# Beambreak_Array_S_-_Receiver.net
KiCad netlist of a schematic drawn in Altium Designer
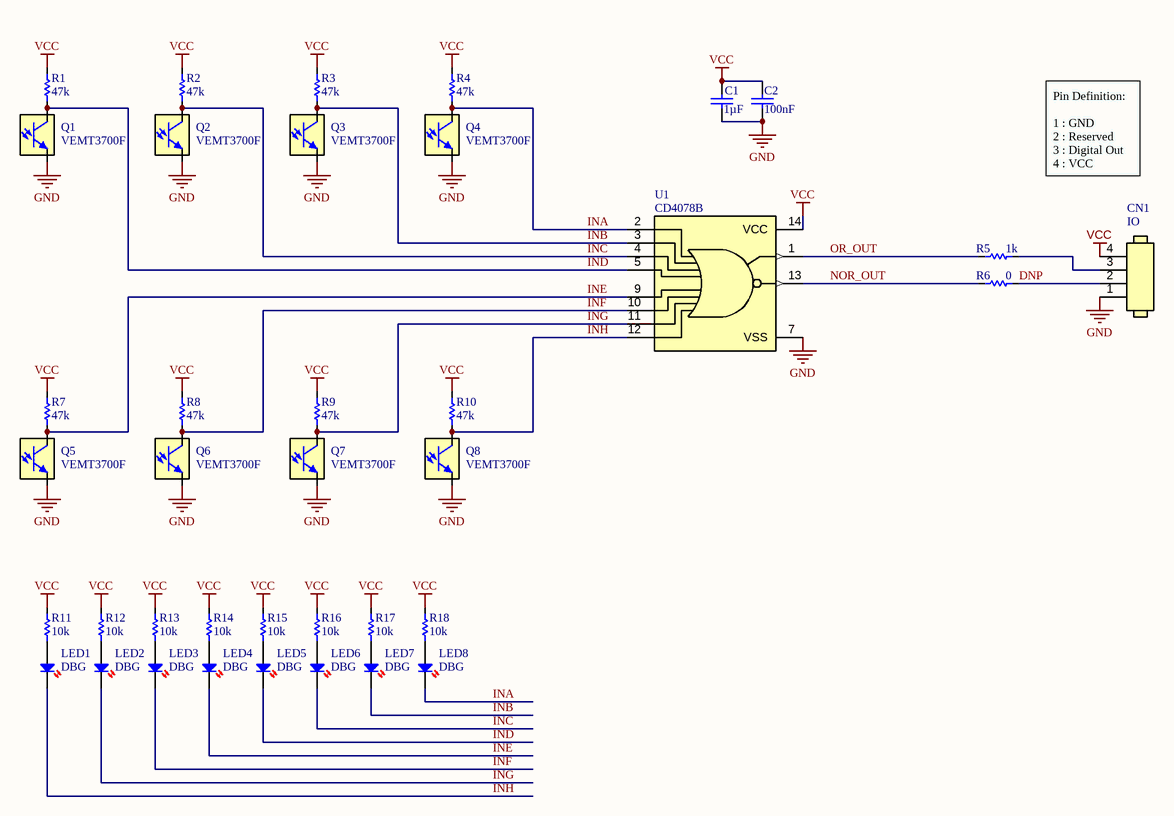
[diagram p0: Beambreak Array S - Receiver.SchDoc]

(export (version "E")
  (design (tool "Eeschema 10.0.6"))
  (components
    (comp (ref "C1")
      (value "1µF")
      (footprint "CAP_CHIP_0603")
      (description "0603 Multilayer Ceramic Capacitors MLCC")
      (fields (field (name "PARTNUMBER") "CL10A105KB8NNNC") (field (name "TOLERANCE") "10%"))
      (libsource (lib "Sainsbury Wellcome Centre") (part "Cap"))
    )
    (comp (ref "C2")
      (value "100nF")
      (footprint "CAP_CHIP_0603")
      (description "0603 Multilayer Ceramic Capacitors MLCC")
      (fields (field (name "TOLERANCE") "10%") (field (name "PARTNUMBER") "CC0603KRX7R9BB104"))
      (libsource (lib "Sainsbury Wellcome Centre") (part "Cap"))
    )
    (comp (ref "CN1")
      (value "IO")
      (footprint "MOLEX_1.25_4P")
      (description "Conn Shrouded Header (3 Sides) HDR 4 POS 1.25mm Solder ST Top Entry SMD PicoBlade™ T/R")
      (fields (field (name "PARTNUMBER") "53398-0471"))
      (libsource (lib "Sainsbury Wellcome Centre") (part "Wire to Board 1x4"))
    )
    (comp (ref "LED1")
      (value "DBG")
      (footprint "LED_CHIP_0805")
      (description "Red 0805 Light Emitting Diodes (LED) ROHS")
      (fields (field (name "PARTNUMBER") "NCD0805R1"))
      (libsource (lib "Sainsbury Wellcome Centre") (part "LED-RED"))
    )
    (comp (ref "LED2")
      (value "DBG")
      (footprint "LED_CHIP_0805")
      (description "Red 0805 Light Emitting Diodes (LED) ROHS")
      (fields (field (name "PARTNUMBER") "NCD0805R1"))
      (libsource (lib "Sainsbury Wellcome Centre") (part "LED-RED"))
    )
    (comp (ref "LED3")
      (value "DBG")
      (footprint "LED_CHIP_0805")
      (description "Red 0805 Light Emitting Diodes (LED) ROHS")
      (fields (field (name "PARTNUMBER") "NCD0805R1"))
      (libsource (lib "Sainsbury Wellcome Centre") (part "LED-RED"))
    )
    (comp (ref "LED4")
      (value "DBG")
      (footprint "LED_CHIP_0805")
      (description "Red 0805 Light Emitting Diodes (LED) ROHS")
      (fields (field (name "PARTNUMBER") "NCD0805R1"))
      (libsource (lib "Sainsbury Wellcome Centre") (part "LED-RED"))
    )
    (comp (ref "LED5")
      (value "DBG")
      (footprint "LED_CHIP_0805")
      (description "Red 0805 Light Emitting Diodes (LED) ROHS")
      (fields (field (name "PARTNUMBER") "NCD0805R1"))
      (libsource (lib "Sainsbury Wellcome Centre") (part "LED-RED"))
    )
    (comp (ref "LED6")
      (value "DBG")
      (footprint "LED_CHIP_0805")
      (description "Red 0805 Light Emitting Diodes (LED) ROHS")
      (fields (field (name "PARTNUMBER") "NCD0805R1"))
      (libsource (lib "Sainsbury Wellcome Centre") (part "LED-RED"))
    )
    (comp (ref "LED7")
      (value "DBG")
      (footprint "LED_CHIP_0805")
      (description "Red 0805 Light Emitting Diodes (LED) ROHS")
      (fields (field (name "PARTNUMBER") "NCD0805R1"))
      (libsource (lib "Sainsbury Wellcome Centre") (part "LED-RED"))
    )
    (comp (ref "LED8")
      (value "DBG")
      (footprint "LED_CHIP_0805")
      (description "Red 0805 Light Emitting Diodes (LED) ROHS")
      (fields (field (name "PARTNUMBER") "NCD0805R1"))
      (libsource (lib "Sainsbury Wellcome Centre") (part "LED-RED"))
    )
    (comp (ref "Q1")
      (value "VEMT3700F")
      (footprint "PT_3528_NPN")
      (description "No Phototransistor IR Chip Silicon 940nm 2-Pin PLCC T/R")
      (fields (field (name "PARTNUMBER") "VEMT3700F-GS08"))
      (libsource (lib "Sainsbury Wellcome Centre") (part "Phototransistors_1C2E"))
    )
    (comp (ref "Q2")
      (value "VEMT3700F")
      (footprint "PT_3528_NPN")
      (description "No Phototransistor IR Chip Silicon 940nm 2-Pin PLCC T/R")
      (fields (field (name "PARTNUMBER") "VEMT3700F-GS08"))
      (libsource (lib "Sainsbury Wellcome Centre") (part "Phototransistors_1C2E"))
    )
    (comp (ref "Q3")
      (value "VEMT3700F")
      (footprint "PT_3528_NPN")
      (description "No Phototransistor IR Chip Silicon 940nm 2-Pin PLCC T/R")
      (fields (field (name "PARTNUMBER") "VEMT3700F-GS08"))
      (libsource (lib "Sainsbury Wellcome Centre") (part "Phototransistors_1C2E"))
    )
    (comp (ref "Q4")
      (value "VEMT3700F")
      (footprint "PT_3528_NPN")
      (description "No Phototransistor IR Chip Silicon 940nm 2-Pin PLCC T/R")
      (fields (field (name "PARTNUMBER") "VEMT3700F-GS08"))
      (libsource (lib "Sainsbury Wellcome Centre") (part "Phototransistors_1C2E"))
    )
    (comp (ref "Q5")
      (value "VEMT3700F")
      (footprint "PT_3528_NPN")
      (description "No Phototransistor IR Chip Silicon 940nm 2-Pin PLCC T/R")
      (fields (field (name "PARTNUMBER") "VEMT3700F-GS08"))
      (libsource (lib "Sainsbury Wellcome Centre") (part "Phototransistors_1C2E"))
    )
    (comp (ref "Q6")
      (value "VEMT3700F")
      (footprint "PT_3528_NPN")
      (description "No Phototransistor IR Chip Silicon 940nm 2-Pin PLCC T/R")
      (fields (field (name "PARTNUMBER") "VEMT3700F-GS08"))
      (libsource (lib "Sainsbury Wellcome Centre") (part "Phototransistors_1C2E"))
    )
    (comp (ref "Q7")
      (value "VEMT3700F")
      (footprint "PT_3528_NPN")
      (description "No Phototransistor IR Chip Silicon 940nm 2-Pin PLCC T/R")
      (fields (field (name "PARTNUMBER") "VEMT3700F-GS08"))
      (libsource (lib "Sainsbury Wellcome Centre") (part "Phototransistors_1C2E"))
    )
    (comp (ref "Q8")
      (value "VEMT3700F")
      (footprint "PT_3528_NPN")
      (description "No Phototransistor IR Chip Silicon 940nm 2-Pin PLCC T/R")
      (fields (field (name "PARTNUMBER") "VEMT3700F-GS08"))
      (libsource (lib "Sainsbury Wellcome Centre") (part "Phototransistors_1C2E"))
    )
    (comp (ref "R1")
      (value "47k")
      (footprint "RES_CHIP_0603")
      (description "100mW Thick Film Resistors 75V ±100ppm/℃ ±1% 0603 Chip Resistor")
      (fields (field (name "TOLERANCE") "1%") (field (name "PARTNUMBER") "0603WAF4702T5E"))
      (libsource (lib "Sainsbury Wellcome Centre") (part "Res"))
    )
    (comp (ref "R2")
      (value "47k")
      (footprint "RES_CHIP_0603")
      (description "100mW Thick Film Resistors 75V ±100ppm/℃ ±1% 0603 Chip Resistor")
      (fields (field (name "TOLERANCE") "1%") (field (name "PARTNUMBER") "0603WAF4702T5E"))
      (libsource (lib "Sainsbury Wellcome Centre") (part "Res"))
    )
    (comp (ref "R3")
      (value "47k")
      (footprint "RES_CHIP_0603")
      (description "100mW Thick Film Resistors 75V ±100ppm/℃ ±1% 0603 Chip Resistor")
      (fields (field (name "TOLERANCE") "1%") (field (name "PARTNUMBER") "0603WAF4702T5E"))
      (libsource (lib "Sainsbury Wellcome Centre") (part "Res"))
    )
    (comp (ref "R4")
      (value "47k")
      (footprint "RES_CHIP_0603")
      (description "100mW Thick Film Resistors 75V ±100ppm/℃ ±1% 0603 Chip Resistor")
      (fields (field (name "TOLERANCE") "1%") (field (name "PARTNUMBER") "0603WAF4702T5E"))
      (libsource (lib "Sainsbury Wellcome Centre") (part "Res"))
    )
    (comp (ref "R5")
      (value "1k")
      (footprint "RES_CHIP_0603")
      (description "100mW Thick Film Resistors 75V ±100ppm/℃ ±1% 0603 Chip Resistor")
      (fields (field (name "PARTNUMBER") "0603WAF1001T5E") (field (name "TOLERANCE") "1%"))
      (libsource (lib "Sainsbury Wellcome Centre") (part "Res"))
    )
    (comp (ref "R6")
      (value "0")
      (footprint "RES_CHIP_0603")
      (description "100mW Thick Film Resistors 75V ±100ppm/℃ ±1% 0603 Chip Resistor")
      (fields
        (field (name "TOLERANCE") "1%")
        (field (name "PARTNUMBER") "0603WAF0000T5E")
        (field (name "LCSC PART N.") "DNP")
      )
      (libsource (lib "Sainsbury Wellcome Centre") (part "Res"))
    )
    (comp (ref "R7")
      (value "47k")
      (footprint "RES_CHIP_0603")
      (description "100mW Thick Film Resistors 75V ±100ppm/℃ ±1% 0603 Chip Resistor")
      (fields (field (name "TOLERANCE") "1%") (field (name "PARTNUMBER") "0603WAF4702T5E"))
      (libsource (lib "Sainsbury Wellcome Centre") (part "Res"))
    )
    (comp (ref "R8")
      (value "47k")
      (footprint "RES_CHIP_0603")
      (description "100mW Thick Film Resistors 75V ±100ppm/℃ ±1% 0603 Chip Resistor")
      (fields (field (name "TOLERANCE") "1%") (field (name "PARTNUMBER") "0603WAF4702T5E"))
      (libsource (lib "Sainsbury Wellcome Centre") (part "Res"))
    )
    (comp (ref "R9")
      (value "47k")
      (footprint "RES_CHIP_0603")
      (description "100mW Thick Film Resistors 75V ±100ppm/℃ ±1% 0603 Chip Resistor")
      (fields (field (name "TOLERANCE") "1%") (field (name "PARTNUMBER") "0603WAF4702T5E"))
      (libsource (lib "Sainsbury Wellcome Centre") (part "Res"))
    )
    (comp (ref "R10")
      (value "47k")
      (footprint "RES_CHIP_0603")
      (description "100mW Thick Film Resistors 75V ±100ppm/℃ ±1% 0603 Chip Resistor")
      (fields (field (name "TOLERANCE") "1%") (field (name "PARTNUMBER") "0603WAF4702T5E"))
      (libsource (lib "Sainsbury Wellcome Centre") (part "Res"))
    )
    (comp (ref "R11")
      (value "10k")
      (footprint "RES_CHIP_0603")
      (description "100mW Thick Film Resistors 75V ±100ppm/℃ ±1% 0603 Chip Resistor")
      (fields (field (name "PARTNUMBER") "0603WAF1002T5E") (field (name "TOLERANCE") "1%"))
      (libsource (lib "Sainsbury Wellcome Centre") (part "Res"))
    )
    (comp (ref "R12")
      (value "10k")
      (footprint "RES_CHIP_0603")
      (description "100mW Thick Film Resistors 75V ±100ppm/℃ ±1% 0603 Chip Resistor")
      (fields (field (name "PARTNUMBER") "0603WAF1002T5E") (field (name "TOLERANCE") "1%"))
      (libsource (lib "Sainsbury Wellcome Centre") (part "Res"))
    )
    (comp (ref "R13")
      (value "10k")
      (footprint "RES_CHIP_0603")
      (description "100mW Thick Film Resistors 75V ±100ppm/℃ ±1% 0603 Chip Resistor")
      (fields (field (name "PARTNUMBER") "0603WAF1002T5E") (field (name "TOLERANCE") "1%"))
      (libsource (lib "Sainsbury Wellcome Centre") (part "Res"))
    )
    (comp (ref "R14")
      (value "10k")
      (footprint "RES_CHIP_0603")
      (description "100mW Thick Film Resistors 75V ±100ppm/℃ ±1% 0603 Chip Resistor")
      (fields (field (name "PARTNUMBER") "0603WAF1002T5E") (field (name "TOLERANCE") "1%"))
      (libsource (lib "Sainsbury Wellcome Centre") (part "Res"))
    )
    (comp (ref "R15")
      (value "10k")
      (footprint "RES_CHIP_0603")
      (description "100mW Thick Film Resistors 75V ±100ppm/℃ ±1% 0603 Chip Resistor")
      (fields (field (name "PARTNUMBER") "0603WAF1002T5E") (field (name "TOLERANCE") "1%"))
      (libsource (lib "Sainsbury Wellcome Centre") (part "Res"))
    )
    (comp (ref "R16")
      (value "10k")
      (footprint "RES_CHIP_0603")
      (description "100mW Thick Film Resistors 75V ±100ppm/℃ ±1% 0603 Chip Resistor")
      (fields (field (name "PARTNUMBER") "0603WAF1002T5E") (field (name "TOLERANCE") "1%"))
      (libsource (lib "Sainsbury Wellcome Centre") (part "Res"))
    )
    (comp (ref "R17")
      (value "10k")
      (footprint "RES_CHIP_0603")
      (description "100mW Thick Film Resistors 75V ±100ppm/℃ ±1% 0603 Chip Resistor")
      (fields (field (name "PARTNUMBER") "0603WAF1002T5E") (field (name "TOLERANCE") "1%"))
      (libsource (lib "Sainsbury Wellcome Centre") (part "Res"))
    )
    (comp (ref "R18")
      (value "10k")
      (footprint "RES_CHIP_0603")
      (description "100mW Thick Film Resistors 75V ±100ppm/℃ ±1% 0603 Chip Resistor")
      (fields (field (name "PARTNUMBER") "0603WAF1002T5E") (field (name "TOLERANCE") "1%"))
      (libsource (lib "Sainsbury Wellcome Centre") (part "Res"))
    )
    (comp (ref "U1")
      (value "CD4078B")
      (footprint "SOIC14")
      (description "IC GATE NOR/OR 8INPUT 14SOIC NOR/OR Gate Configurable 1 Circuit 8 Input 14-SOIC")
      (fields (field (name "PARTNUMBER") "CD4078BM96"))
      (libsource (lib "Sainsbury Wellcome Centre") (part "CD4078B"))
    )
  )
  (nets
    (net (code "1") (name "/INA") (class "Default")
      (node (ref "LED8") (pin "1") (pinfunction "K_1") (pintype "passive"))
      (node (ref "Q4") (pin "1") (pinfunction "C_1") (pintype "passive"))
      (node (ref "R4") (pin "1") (pinfunction "1_1") (pintype "passive"))
      (node (ref "U1") (pin "2") (pinfunction "1A_2") (pintype "passive"))
    )
    (net (code "2") (name "/INB") (class "Default")
      (node (ref "LED7") (pin "1") (pinfunction "K_1") (pintype "passive"))
      (node (ref "Q3") (pin "1") (pinfunction "C_1") (pintype "passive"))
      (node (ref "R3") (pin "1") (pinfunction "1_1") (pintype "passive"))
      (node (ref "U1") (pin "3") (pinfunction "1A_3") (pintype "passive"))
    )
    (net (code "3") (name "/INC") (class "Default")
      (node (ref "LED6") (pin "1") (pinfunction "K_1") (pintype "passive"))
      (node (ref "Q2") (pin "1") (pinfunction "C_1") (pintype "passive"))
      (node (ref "R2") (pin "1") (pinfunction "1_1") (pintype "passive"))
      (node (ref "U1") (pin "4") (pinfunction "1A_4") (pintype "passive"))
    )
    (net (code "4") (name "/IND") (class "Default")
      (node (ref "LED5") (pin "1") (pinfunction "K_1") (pintype "passive"))
      (node (ref "Q1") (pin "1") (pinfunction "C_1") (pintype "passive"))
      (node (ref "R1") (pin "1") (pinfunction "1_1") (pintype "passive"))
      (node (ref "U1") (pin "5") (pinfunction "1A_5") (pintype "passive"))
    )
    (net (code "5") (name "/INE") (class "Default")
      (node (ref "LED4") (pin "1") (pinfunction "K_1") (pintype "passive"))
      (node (ref "Q5") (pin "1") (pinfunction "C_1") (pintype "passive"))
      (node (ref "R7") (pin "1") (pinfunction "1_1") (pintype "passive"))
      (node (ref "U1") (pin "9") (pinfunction "1B_9") (pintype "passive"))
    )
    (net (code "6") (name "/INF") (class "Default")
      (node (ref "LED3") (pin "1") (pinfunction "K_1") (pintype "passive"))
      (node (ref "Q6") (pin "1") (pinfunction "C_1") (pintype "passive"))
      (node (ref "R8") (pin "1") (pinfunction "1_1") (pintype "passive"))
      (node (ref "U1") (pin "10") (pinfunction "2A_10") (pintype "passive"))
    )
    (net (code "7") (name "/ING") (class "Default")
      (node (ref "LED2") (pin "1") (pinfunction "K_1") (pintype "passive"))
      (node (ref "Q7") (pin "1") (pinfunction "C_1") (pintype "passive"))
      (node (ref "R9") (pin "1") (pinfunction "1_1") (pintype "passive"))
      (node (ref "U1") (pin "11") (pinfunction "2B_11") (pintype "passive"))
    )
    (net (code "8") (name "/INH") (class "Default")
      (node (ref "LED1") (pin "1") (pinfunction "K_1") (pintype "passive"))
      (node (ref "Q8") (pin "1") (pinfunction "C_1") (pintype "passive"))
      (node (ref "R10") (pin "1") (pinfunction "1_1") (pintype "passive"))
      (node (ref "U1") (pin "12") (pinfunction "1A_12") (pintype "passive"))
    )
    (net (code "9") (name "/NOR_OUT") (class "Default")
      (node (ref "R6") (pin "1") (pinfunction "1_1") (pintype "passive"))
      (node (ref "U1") (pin "13") (pinfunction "OUT_13") (pintype "output"))
    )
    (net (code "10") (name "/OR_OUT") (class "Default")
      (node (ref "R5") (pin "2") (pinfunction "2_2") (pintype "passive"))
      (node (ref "U1") (pin "1") (pinfunction "~{OUT}_1") (pintype "output"))
    )
    (net (code "11") (name "GND") (class "Default")
      (node (ref "C1") (pin "2") (pinfunction "2_2") (pintype "passive"))
      (node (ref "C2") (pin "1") (pinfunction "1_1") (pintype "passive"))
      (node (ref "CN1") (pin "1") (pinfunction "1_1") (pintype "passive"))
      (node (ref "Q1") (pin "2") (pinfunction "E_2") (pintype "passive"))
      (node (ref "Q2") (pin "2") (pinfunction "E_2") (pintype "passive"))
      (node (ref "Q3") (pin "2") (pinfunction "E_2") (pintype "passive"))
      (node (ref "Q4") (pin "2") (pinfunction "E_2") (pintype "passive"))
      (node (ref "Q5") (pin "2") (pinfunction "E_2") (pintype "passive"))
      (node (ref "Q6") (pin "2") (pinfunction "E_2") (pintype "passive"))
      (node (ref "Q7") (pin "2") (pinfunction "E_2") (pintype "passive"))
      (node (ref "Q8") (pin "2") (pinfunction "E_2") (pintype "passive"))
      (node (ref "U1") (pin "7") (pinfunction "VSS_7") (pintype "power_in"))
    )
    (net (code "12") (name "Net-(CN1-Pad2)") (class "Default")
      (node (ref "CN1") (pin "2") (pinfunction "2_2") (pintype "passive"))
      (node (ref "R6") (pin "2") (pinfunction "2_2") (pintype "passive"))
    )
    (net (code "13") (name "Net-(CN1-Pad3)") (class "Default")
      (node (ref "CN1") (pin "3") (pinfunction "3_3") (pintype "passive"))
      (node (ref "R5") (pin "1") (pinfunction "1_1") (pintype "passive"))
    )
    (net (code "14") (name "Net-(LED1-A)") (class "Default")
      (node (ref "LED1") (pin "2") (pinfunction "A_2") (pintype "passive"))
      (node (ref "R11") (pin "1") (pinfunction "1_1") (pintype "passive"))
    )
    (net (code "15") (name "Net-(LED2-A)") (class "Default")
      (node (ref "LED2") (pin "2") (pinfunction "A_2") (pintype "passive"))
      (node (ref "R12") (pin "1") (pinfunction "1_1") (pintype "passive"))
    )
    (net (code "16") (name "Net-(LED3-A)") (class "Default")
      (node (ref "LED3") (pin "2") (pinfunction "A_2") (pintype "passive"))
      (node (ref "R13") (pin "1") (pinfunction "1_1") (pintype "passive"))
    )
    (net (code "17") (name "Net-(LED4-A)") (class "Default")
      (node (ref "LED4") (pin "2") (pinfunction "A_2") (pintype "passive"))
      (node (ref "R14") (pin "1") (pinfunction "1_1") (pintype "passive"))
    )
    (net (code "18") (name "Net-(LED5-A)") (class "Default")
      (node (ref "LED5") (pin "2") (pinfunction "A_2") (pintype "passive"))
      (node (ref "R15") (pin "1") (pinfunction "1_1") (pintype "passive"))
    )
    (net (code "19") (name "Net-(LED6-A)") (class "Default")
      (node (ref "LED6") (pin "2") (pinfunction "A_2") (pintype "passive"))
      (node (ref "R16") (pin "1") (pinfunction "1_1") (pintype "passive"))
    )
    (net (code "20") (name "Net-(LED7-A)") (class "Default")
      (node (ref "LED7") (pin "2") (pinfunction "A_2") (pintype "passive"))
      (node (ref "R17") (pin "1") (pinfunction "1_1") (pintype "passive"))
    )
    (net (code "21") (name "Net-(LED8-A)") (class "Default")
      (node (ref "LED8") (pin "2") (pinfunction "A_2") (pintype "passive"))
      (node (ref "R18") (pin "1") (pinfunction "1_1") (pintype "passive"))
    )
    (net (code "22") (name "VCC") (class "Default")
      (node (ref "C1") (pin "1") (pinfunction "1_1") (pintype "passive"))
      (node (ref "C2") (pin "2") (pinfunction "2_2") (pintype "passive"))
      (node (ref "CN1") (pin "4") (pinfunction "4_4") (pintype "passive"))
      (node (ref "R1") (pin "2") (pinfunction "2_2") (pintype "passive"))
      (node (ref "R10") (pin "2") (pinfunction "2_2") (pintype "passive"))
      (node (ref "R11") (pin "2") (pinfunction "2_2") (pintype "passive"))
      (node (ref "R12") (pin "2") (pinfunction "2_2") (pintype "passive"))
      (node (ref "R13") (pin "2") (pinfunction "2_2") (pintype "passive"))
      (node (ref "R14") (pin "2") (pinfunction "2_2") (pintype "passive"))
      (node (ref "R15") (pin "2") (pinfunction "2_2") (pintype "passive"))
      (node (ref "R16") (pin "2") (pinfunction "2_2") (pintype "passive"))
      (node (ref "R17") (pin "2") (pinfunction "2_2") (pintype "passive"))
      (node (ref "R18") (pin "2") (pinfunction "2_2") (pintype "passive"))
      (node (ref "R2") (pin "2") (pinfunction "2_2") (pintype "passive"))
      (node (ref "R3") (pin "2") (pinfunction "2_2") (pintype "passive"))
      (node (ref "R4") (pin "2") (pinfunction "2_2") (pintype "passive"))
      (node (ref "R7") (pin "2") (pinfunction "2_2") (pintype "passive"))
      (node (ref "R8") (pin "2") (pinfunction "2_2") (pintype "passive"))
      (node (ref "R9") (pin "2") (pinfunction "2_2") (pintype "passive"))
      (node (ref "U1") (pin "14") (pinfunction "VCC_14") (pintype "power_in"))
    )
  )
)
